# snorlax_velostat.net
KiCad netlist of a schematic drawn in EAGLE
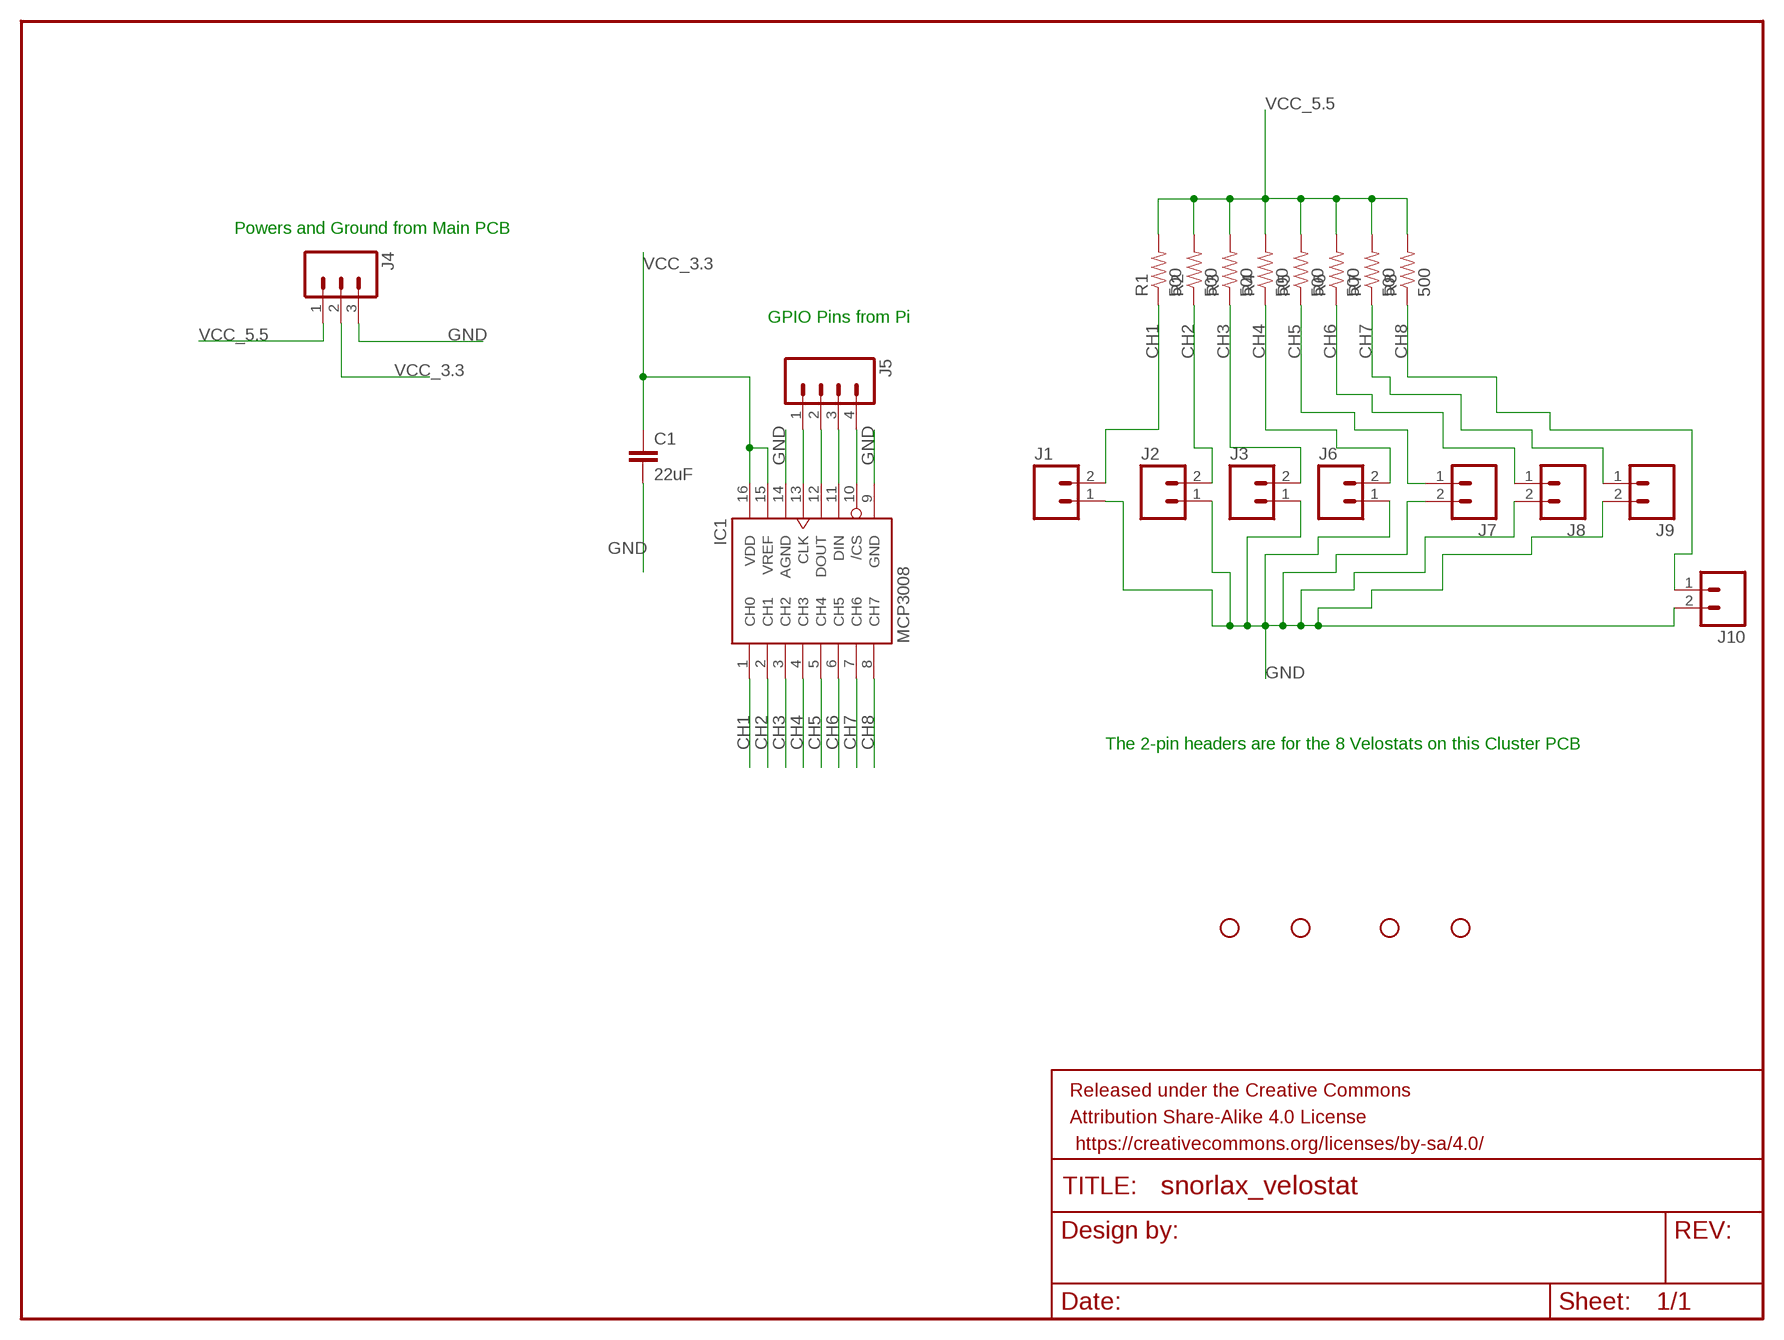
[diagram p0: schematic, sheet 1]

(export (version "E")
  (design (tool "Eeschema 10.0.6"))
  (components
    (comp (ref "C1")
      (value "22uF")
      (footprint "eagle-import:1206")
      (libsource (lib "eagle-import") (part "CAP1206"))
    )
    (comp (ref "FRAME1")
      (value "FRAME-LETTER")
      (footprint "eagle-import:CREATIVE_COMMONS")
      (libsource (lib "eagle-import") (part "FRAME-LETTER"))
    )
    (comp (ref "H1")
      (value "STAND-OFF")
      (footprint "eagle-import:STAND-OFF")
      (libsource (lib "eagle-import") (part "STAND-OFF"))
    )
    (comp (ref "H2")
      (value "STAND-OFF")
      (footprint "eagle-import:STAND-OFF")
      (libsource (lib "eagle-import") (part "STAND-OFF"))
    )
    (comp (ref "H3")
      (value "STAND-OFF")
      (footprint "eagle-import:STAND-OFF")
      (libsource (lib "eagle-import") (part "STAND-OFF"))
    )
    (comp (ref "H4")
      (value "STAND-OFF")
      (footprint "eagle-import:STAND-OFF")
      (libsource (lib "eagle-import") (part "STAND-OFF"))
    )
    (comp (ref "IC1")
      (value "MCP3008")
      (footprint "eagle-import:DIL16")
      (libsource (lib "eagle-import") (part "MCP3008"))
    )
    (comp (ref "J1")
      (value "M02LOCK")
      (footprint "eagle-import:1X02_LOCK")
      (libsource (lib "eagle-import") (part "M02LOCK"))
    )
    (comp (ref "J2")
      (value "M02LOCK")
      (footprint "eagle-import:1X02_LOCK")
      (libsource (lib "eagle-import") (part "M02LOCK"))
    )
    (comp (ref "J3")
      (value "M02LOCK")
      (footprint "eagle-import:1X02_LOCK")
      (libsource (lib "eagle-import") (part "M02LOCK"))
    )
    (comp (ref "J4")
      (value "M03LOCK")
      (footprint "eagle-import:1X03_LOCK")
      (libsource (lib "eagle-import") (part "M03LOCK"))
    )
    (comp (ref "J5")
      (value "M04LOCK")
      (footprint "eagle-import:1X04_LOCK")
      (libsource (lib "eagle-import") (part "M04LOCK"))
    )
    (comp (ref "J6")
      (value "M02LOCK")
      (footprint "eagle-import:1X02_LOCK")
      (libsource (lib "eagle-import") (part "M02LOCK"))
    )
    (comp (ref "J7")
      (value "M02LOCK")
      (footprint "eagle-import:1X02_LOCK")
      (libsource (lib "eagle-import") (part "M02LOCK"))
    )
    (comp (ref "J8")
      (value "M02LOCK")
      (footprint "eagle-import:1X02_LOCK")
      (libsource (lib "eagle-import") (part "M02LOCK"))
    )
    (comp (ref "J9")
      (value "M02LOCK")
      (footprint "eagle-import:1X02_LOCK")
      (libsource (lib "eagle-import") (part "M02LOCK"))
    )
    (comp (ref "J10")
      (value "M02LOCK")
      (footprint "eagle-import:1X02_LOCK")
      (libsource (lib "eagle-import") (part "M02LOCK"))
    )
    (comp (ref "R1")
      (value "500")
      (footprint "eagle-import:1206")
      (libsource (lib "eagle-import") (part "RESISTOR1206"))
    )
    (comp (ref "R2")
      (value "500")
      (footprint "eagle-import:1206")
      (libsource (lib "eagle-import") (part "RESISTOR1206"))
    )
    (comp (ref "R3")
      (value "500")
      (footprint "eagle-import:1206")
      (libsource (lib "eagle-import") (part "RESISTOR1206"))
    )
    (comp (ref "R4")
      (value "500")
      (footprint "eagle-import:1206")
      (libsource (lib "eagle-import") (part "RESISTOR1206"))
    )
    (comp (ref "R5")
      (value "500")
      (footprint "eagle-import:1206")
      (libsource (lib "eagle-import") (part "RESISTOR1206"))
    )
    (comp (ref "R6")
      (value "500")
      (footprint "eagle-import:1206")
      (libsource (lib "eagle-import") (part "RESISTOR1206"))
    )
    (comp (ref "R7")
      (value "500")
      (footprint "eagle-import:1206")
      (libsource (lib "eagle-import") (part "RESISTOR1206"))
    )
    (comp (ref "R8")
      (value "500")
      (footprint "eagle-import:1206")
      (libsource (lib "eagle-import") (part "RESISTOR1206"))
    )
  )
  (nets
    (net (code "1") (name "/CH1") (class "Default")
      (node (ref "IC1") (pin "1") (pinfunction "CH0_1") (pintype "input"))
      (node (ref "J1") (pin "2") (pinfunction "2_2") (pintype "passive"))
      (node (ref "R1") (pin "1") (pinfunction "1_1") (pintype "passive"))
    )
    (net (code "2") (name "/CH2") (class "Default")
      (node (ref "IC1") (pin "2") (pinfunction "CH1_2") (pintype "input"))
      (node (ref "J2") (pin "2") (pinfunction "2_2") (pintype "passive"))
      (node (ref "R2") (pin "1") (pinfunction "1_1") (pintype "passive"))
    )
    (net (code "3") (name "/CH3") (class "Default")
      (node (ref "IC1") (pin "3") (pinfunction "CH2_3") (pintype "input"))
      (node (ref "J3") (pin "2") (pinfunction "2_2") (pintype "passive"))
      (node (ref "R3") (pin "1") (pinfunction "1_1") (pintype "passive"))
    )
    (net (code "4") (name "/CH4") (class "Default")
      (node (ref "IC1") (pin "4") (pinfunction "CH3_4") (pintype "input"))
      (node (ref "J6") (pin "2") (pinfunction "2_2") (pintype "passive"))
      (node (ref "R4") (pin "1") (pinfunction "1_1") (pintype "passive"))
    )
    (net (code "5") (name "/CH5") (class "Default")
      (node (ref "IC1") (pin "5") (pinfunction "CH4_5") (pintype "input"))
      (node (ref "J7") (pin "1") (pinfunction "1_1") (pintype "passive"))
      (node (ref "R5") (pin "1") (pinfunction "1_1") (pintype "passive"))
    )
    (net (code "6") (name "/CH6") (class "Default")
      (node (ref "IC1") (pin "6") (pinfunction "CH5_6") (pintype "input"))
      (node (ref "J8") (pin "1") (pinfunction "1_1") (pintype "passive"))
      (node (ref "R6") (pin "1") (pinfunction "1_1") (pintype "passive"))
    )
    (net (code "7") (name "/CH7") (class "Default")
      (node (ref "IC1") (pin "7") (pinfunction "CH6_7") (pintype "input"))
      (node (ref "J9") (pin "1") (pinfunction "1_1") (pintype "passive"))
      (node (ref "R7") (pin "1") (pinfunction "1_1") (pintype "passive"))
    )
    (net (code "8") (name "/CH8") (class "Default")
      (node (ref "IC1") (pin "8") (pinfunction "CH7_8") (pintype "input"))
      (node (ref "J10") (pin "1") (pinfunction "1_1") (pintype "passive"))
      (node (ref "R8") (pin "1") (pinfunction "1_1") (pintype "passive"))
    )
    (net (code "9") (name "/GND") (class "Default")
      (node (ref "C1") (pin "2") (pinfunction "2_2") (pintype "passive"))
      (node (ref "IC1") (pin "14") (pinfunction "AGND_14") (pintype "power_in"))
      (node (ref "IC1") (pin "9") (pinfunction "GND_9") (pintype "power_in"))
      (node (ref "J1") (pin "1") (pinfunction "1_1") (pintype "passive"))
      (node (ref "J10") (pin "2") (pinfunction "2_2") (pintype "passive"))
      (node (ref "J2") (pin "1") (pinfunction "1_1") (pintype "passive"))
      (node (ref "J3") (pin "1") (pinfunction "1_1") (pintype "passive"))
      (node (ref "J4") (pin "3") (pinfunction "3_3") (pintype "passive"))
      (node (ref "J6") (pin "1") (pinfunction "1_1") (pintype "passive"))
      (node (ref "J7") (pin "2") (pinfunction "2_2") (pintype "passive"))
      (node (ref "J8") (pin "2") (pinfunction "2_2") (pintype "passive"))
      (node (ref "J9") (pin "2") (pinfunction "2_2") (pintype "passive"))
    )
    (net (code "10") (name "/VCC_3.3") (class "Default")
      (node (ref "C1") (pin "1") (pinfunction "1_1") (pintype "passive"))
      (node (ref "IC1") (pin "15") (pinfunction "VREF_15") (pintype "input"))
      (node (ref "IC1") (pin "16") (pinfunction "VDD_16") (pintype "power_in"))
      (node (ref "J4") (pin "2") (pinfunction "2_2") (pintype "passive"))
    )
    (net (code "11") (name "/VCC_5.5") (class "Default")
      (node (ref "J4") (pin "1") (pinfunction "1_1") (pintype "passive"))
      (node (ref "R1") (pin "2") (pinfunction "2_2") (pintype "passive"))
      (node (ref "R2") (pin "2") (pinfunction "2_2") (pintype "passive"))
      (node (ref "R3") (pin "2") (pinfunction "2_2") (pintype "passive"))
      (node (ref "R4") (pin "2") (pinfunction "2_2") (pintype "passive"))
      (node (ref "R5") (pin "2") (pinfunction "2_2") (pintype "passive"))
      (node (ref "R6") (pin "2") (pinfunction "2_2") (pintype "passive"))
      (node (ref "R7") (pin "2") (pinfunction "2_2") (pintype "passive"))
      (node (ref "R8") (pin "2") (pinfunction "2_2") (pintype "passive"))
    )
    (net (code "12") (name "Net-(IC1-CLK)") (class "Default")
      (node (ref "IC1") (pin "13") (pinfunction "CLK_13") (pintype "input"))
      (node (ref "J5") (pin "1") (pinfunction "1_1") (pintype "passive"))
    )
    (net (code "13") (name "Net-(IC1-DIN)") (class "Default")
      (node (ref "IC1") (pin "11") (pinfunction "DIN_11") (pintype "input"))
      (node (ref "J5") (pin "3") (pinfunction "3_3") (pintype "passive"))
    )
    (net (code "14") (name "Net-(IC1-DOUT)") (class "Default")
      (node (ref "IC1") (pin "12") (pinfunction "DOUT_12") (pintype "output"))
      (node (ref "J5") (pin "2") (pinfunction "2_2") (pintype "passive"))
    )
    (net (code "15") (name "Net-(IC1-{slash}CS)") (class "Default")
      (node (ref "IC1") (pin "10") (pinfunction "/CS_10") (pintype "input"))
      (node (ref "J5") (pin "4") (pinfunction "4_4") (pintype "passive"))
    )
  )
)
